# picoAvaR3.net
KiCad netlist of a schematic drawn in EAGLE
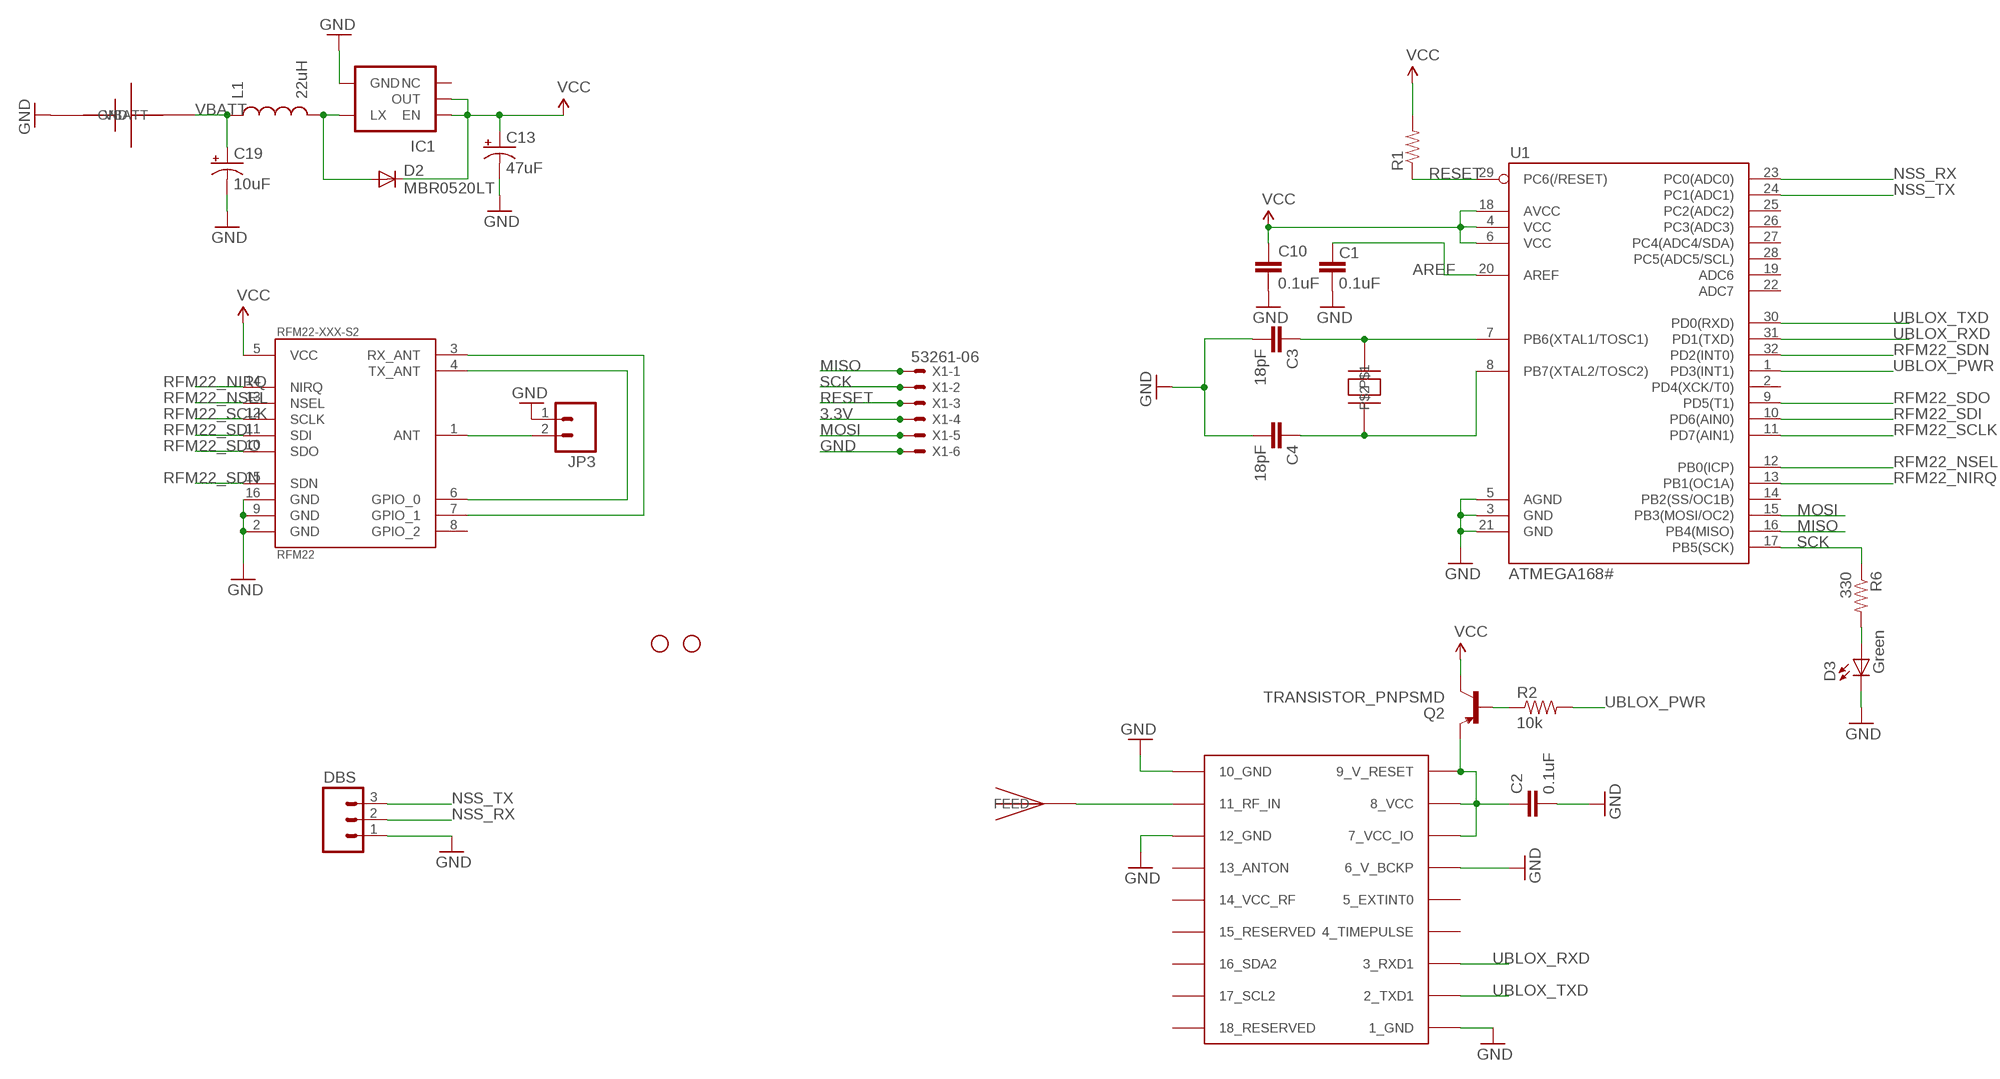
[diagram p0: schematic, sheet 1]

(export (version "E")
  (design (tool "Eeschema 10.0.6"))
  (components
    (comp (ref "C1")
      (value "0.1uF")
      (footprint "eagle-import:0402-CAP")
      (libsource (lib "eagle-import") (part "CAP0402-CAP"))
    )
    (comp (ref "C2")
      (value "0.1uF")
      (footprint "eagle-import:0402-CAP")
      (libsource (lib "eagle-import") (part "CAP0402-CAP"))
    )
    (comp (ref "C3")
      (value "18pF")
      (footprint "eagle-import:0402-CAP")
      (libsource (lib "eagle-import") (part "CAP0402-CAP"))
    )
    (comp (ref "C4")
      (value "18pF")
      (footprint "eagle-import:0402-CAP")
      (libsource (lib "eagle-import") (part "CAP0402-CAP"))
    )
    (comp (ref "C10")
      (value "0.1uF")
      (footprint "eagle-import:0402-CAP")
      (libsource (lib "eagle-import") (part "CAP0402-CAP"))
    )
    (comp (ref "C13")
      (value "47uF")
      (footprint "eagle-import:EIA3216")
      (libsource (lib "eagle-import") (part "CAP_POL1206"))
    )
    (comp (ref "C19")
      (value "10uF")
      (footprint "eagle-import:EIA3216")
      (libsource (lib "eagle-import") (part "CAP_POL1206"))
    )
    (comp (ref "D2")
      (value "MBR0520LT")
      (footprint "eagle-import:SOD123")
      (libsource (lib "eagle-import") (part "MBR0520LT"))
    )
    (comp (ref "D3")
      (value "Green")
      (footprint "eagle-import:LED-0603")
      (libsource (lib "eagle-import") (part "LED0603"))
    )
    (comp (ref "DBS")
      (value "M03PTH")
      (footprint "eagle-import:1X03")
      (libsource (lib "eagle-import") (part "M03PTH"))
    )
    (comp (ref "IC1")
      (value "V_REG_NCP1400SOT23-5")
      (footprint "eagle-import:SOT23-5")
      (libsource (lib "eagle-import") (part "V_REG_NCP1400SOT23-5"))
    )
    (comp (ref "JP1")
      (value "STAND-OFF")
      (footprint "eagle-import:STAND-OFF")
      (libsource (lib "eagle-import") (part "STAND-OFF"))
    )
    (comp (ref "JP2")
      (value "STAND-OFF")
      (footprint "eagle-import:STAND-OFF")
      (libsource (lib "eagle-import") (part "STAND-OFF"))
    )
    (comp (ref "JP3")
      (value "M02PTH")
      (footprint "eagle-import:1X02")
      (libsource (lib "eagle-import") (part "M02PTH"))
    )
    (comp (ref "L1")
      (value "22uH")
      (footprint "eagle-import:1210")
      (libsource (lib "eagle-import") (part "INDUCTOR1210"))
    )
    (comp (ref "Q2")
      (value "TRANSISTOR_PNPSMD")
      (footprint "eagle-import:SOT23-3")
      (libsource (lib "eagle-import") (part "TRANSISTOR_PNPSMD"))
    )
    (comp (ref "R1")
      (value "RESISTOR0402-RES")
      (footprint "eagle-import:0402-RES")
      (libsource (lib "eagle-import") (part "RESISTOR0402-RES"))
    )
    (comp (ref "R2")
      (value "10k")
      (footprint "eagle-import:0402-RES")
      (libsource (lib "eagle-import") (part "RESISTOR0402-RES"))
    )
    (comp (ref "R6")
      (value "330")
      (footprint "eagle-import:0402-RES")
      (libsource (lib "eagle-import") (part "RESISTOR0402-RES"))
    )
    (comp (ref "RFM22-XXX-S2")
      (value "RFM22")
      (footprint "eagle-import:RFM22-XXX-S2")
      (libsource (lib "eagle-import") (part "RFM22"))
    )
    (comp (ref "U$1")
      (value "UBLOX_MAX-6")
      (footprint "eagle-import:UBLOX_MAX-6")
      (libsource (lib "eagle-import") (part "UBLOX_MAX-6"))
    )
    (comp (ref "U$2")
      (value "ABRACON_ABM3_CRYSTAL")
      (footprint "eagle-import:ABRACON_ABM3_CRYSTAL")
      (libsource (lib "eagle-import") (part "ABRACON_ABM3_CRYSTAL"))
    )
    (comp (ref "U$3")
      (value "JTI_ANTENNA-1575AT43A40")
      (footprint "eagle-import:JTI_ANTENNA-1575AT43A40")
      (libsource (lib "eagle-import") (part "JTI_ANTENNA-1575AT43A40"))
    )
    (comp (ref "U$4")
      (value "KEYSTONE-82-AAA-BATTERY-HOLDER")
      (footprint "eagle-import:KEYSTONE-82-AAA-BATTERY")
      (libsource (lib "eagle-import") (part "KEYSTONE-82-AAA-BATTERY-HOLDER"))
    )
    (comp (ref "U1")
      (value "ATMEGA168#")
      (footprint "eagle-import:TQFP32-08")
      (libsource (lib "eagle-import") (part "ATMEGA168"))
    )
    (comp (ref "X1")
      (value "53261-06")
      (footprint "eagle-import:53261-06")
      (libsource (lib "eagle-import") (part "53?-06261"))
    )
  )
  (nets
    (net (code "1") (name "3.3V") (class "Default")
      (node (ref "C10") (pin "1") (pinfunction "1_1") (pintype "passive"))
      (node (ref "C13") (pin "A") (pinfunction "+_A") (pintype "passive"))
      (node (ref "D2") (pin "C") (pinfunction "C_C") (pintype "passive"))
      (node (ref "IC1") (pin "1") (pinfunction "EN_1") (pintype "input"))
      (node (ref "IC1") (pin "2") (pinfunction "OUT_2") (pintype "passive"))
      (node (ref "Q2") (pin "3") (pinfunction "C_3") (pintype "passive"))
      (node (ref "R1") (pin "2") (pinfunction "2_2") (pintype "passive"))
      (node (ref "RFM22-XXX-S2") (pin "5") (pinfunction "VCC_5") (pintype "bidirectional"))
      (node (ref "U1") (pin "18") (pinfunction "AVCC_18") (pintype "bidirectional"))
      (node (ref "U1") (pin "4") (pinfunction "VCC_4") (pintype "bidirectional"))
      (node (ref "U1") (pin "6") (pinfunction "VCC_6") (pintype "bidirectional"))
      (node (ref "X1") (pin "4") (pinfunction "S_4") (pintype "passive"))
    )
    (net (code "2") (name "AREF") (class "Default")
      (node (ref "C1") (pin "2") (pinfunction "2_2") (pintype "passive"))
      (node (ref "U1") (pin "20") (pinfunction "AREF_20") (pintype "bidirectional"))
    )
    (net (code "3") (name "GND") (class "Default")
      (node (ref "C1") (pin "1") (pinfunction "1_1") (pintype "passive"))
      (node (ref "C10") (pin "2") (pinfunction "2_2") (pintype "passive"))
      (node (ref "C13") (pin "C") (pinfunction "-_C") (pintype "passive"))
      (node (ref "C19") (pin "C") (pinfunction "-_C") (pintype "passive"))
      (node (ref "C2") (pin "2") (pinfunction "2_2") (pintype "passive"))
      (node (ref "C3") (pin "2") (pinfunction "2_2") (pintype "passive"))
      (node (ref "C4") (pin "2") (pinfunction "2_2") (pintype "passive"))
      (node (ref "D3") (pin "C") (pinfunction "C_C") (pintype "passive"))
      (node (ref "DBS") (pin "1") (pinfunction "1_1") (pintype "passive"))
      (node (ref "IC1") (pin "4") (pinfunction "GND_4") (pintype "input"))
      (node (ref "JP3") (pin "1") (pinfunction "1_1") (pintype "passive"))
      (node (ref "RFM22-XXX-S2") (pin "16") (pinfunction "GND_16") (pintype "power_in"))
      (node (ref "RFM22-XXX-S2") (pin "2") (pinfunction "GND_2") (pintype "power_in"))
      (node (ref "RFM22-XXX-S2") (pin "9") (pinfunction "GND_9") (pintype "power_in"))
      (node (ref "U$1") (pin "10_GND") (pinfunction "10_GND_10_GND") (pintype "bidirectional"))
      (node (ref "U$1") (pin "12_GND") (pinfunction "12_GND_12_GND") (pintype "bidirectional"))
      (node (ref "U$1") (pin "1_GND") (pinfunction "1_GND_1_GND") (pintype "bidirectional"))
      (node (ref "U$1") (pin "6_V_BCKP") (pinfunction "6_V_BCKP_6_V_BCKP") (pintype "bidirectional"))
      (node (ref "U$4") (pin "GND") (pinfunction "GND_GND") (pintype "bidirectional"))
      (node (ref "U$4") (pin "GND2") (pinfunction "GND_GND2") (pintype "bidirectional"))
      (node (ref "U1") (pin "21") (pinfunction "GND_21") (pintype "bidirectional"))
      (node (ref "U1") (pin "3") (pinfunction "GND_3") (pintype "bidirectional"))
      (node (ref "U1") (pin "5") (pinfunction "AGND_5") (pintype "bidirectional"))
      (node (ref "X1") (pin "6") (pinfunction "S_6") (pintype "passive"))
    )
    (net (code "4") (name "MISO") (class "Default")
      (node (ref "U1") (pin "16") (pinfunction "PB4(MISO)_16") (pintype "bidirectional"))
      (node (ref "X1") (pin "1") (pinfunction "S_1") (pintype "passive"))
    )
    (net (code "5") (name "MOSI") (class "Default")
      (node (ref "U1") (pin "15") (pinfunction "PB3(MOSI/OC2)_15") (pintype "bidirectional"))
      (node (ref "X1") (pin "5") (pinfunction "S_5") (pintype "passive"))
    )
    (net (code "6") (name "NSS_RX") (class "Default")
      (node (ref "DBS") (pin "2") (pinfunction "2_2") (pintype "passive"))
      (node (ref "U1") (pin "23") (pinfunction "PC0(ADC0)_23") (pintype "bidirectional"))
    )
    (net (code "7") (name "NSS_TX") (class "Default")
      (node (ref "DBS") (pin "3") (pinfunction "3_3") (pintype "passive"))
      (node (ref "U1") (pin "24") (pinfunction "PC1(ADC1)_24") (pintype "bidirectional"))
    )
    (net (code "8") (name "Net-(D3-PadA)") (class "Default")
      (node (ref "D3") (pin "A") (pinfunction "A_A") (pintype "passive"))
      (node (ref "R6") (pin "2") (pinfunction "2_2") (pintype "passive"))
    )
    (net (code "9") (name "Net-(IC1-LX)") (class "Default")
      (node (ref "D2") (pin "A") (pinfunction "A_A") (pintype "passive"))
      (node (ref "IC1") (pin "5") (pinfunction "LX_5") (pintype "input"))
      (node (ref "L1") (pin "2") (pinfunction "2_2") (pintype "passive"))
    )
    (net (code "10") (name "Net-(Q2-B)") (class "Default")
      (node (ref "Q2") (pin "1") (pinfunction "B_1") (pintype "passive"))
      (node (ref "R2") (pin "1") (pinfunction "1_1") (pintype "passive"))
    )
    (net (code "11") (name "Net-(Q2-E)") (class "Default")
      (node (ref "C2") (pin "1") (pinfunction "1_1") (pintype "passive"))
      (node (ref "Q2") (pin "2") (pinfunction "E_2") (pintype "passive"))
      (node (ref "U$1") (pin "7_VCC_IO") (pinfunction "7_VCC_IO_7_VCC_IO") (pintype "bidirectional"))
      (node (ref "U$1") (pin "8_VCC") (pinfunction "8_VCC_8_VCC") (pintype "bidirectional"))
      (node (ref "U$1") (pin "9_V_RESET") (pinfunction "9_V_RESET_9_V_RESET") (pintype "bidirectional"))
    )
    (net (code "12") (name "Net-(RFM22-XXX-S2-ANT)") (class "Default")
      (node (ref "JP3") (pin "2") (pinfunction "2_2") (pintype "passive"))
      (node (ref "RFM22-XXX-S2") (pin "1") (pinfunction "ANT_1") (pintype "bidirectional"))
    )
    (net (code "13") (name "Net-(RFM22-XXX-S2-GPIO_0)") (class "Default")
      (node (ref "RFM22-XXX-S2") (pin "4") (pinfunction "TX_ANT_4") (pintype "input"))
      (node (ref "RFM22-XXX-S2") (pin "6") (pinfunction "GPIO_0_6") (pintype "bidirectional"))
    )
    (net (code "14") (name "Net-(RFM22-XXX-S2-GPIO_1)") (class "Default")
      (node (ref "RFM22-XXX-S2") (pin "3") (pinfunction "RX_ANT_3") (pintype "input"))
      (node (ref "RFM22-XXX-S2") (pin "7") (pinfunction "GPIO_1_7") (pintype "bidirectional"))
    )
    (net (code "15") (name "Net-(U$1-Pad11_RF_IN)") (class "Default")
      (node (ref "U$1") (pin "11_RF_IN") (pinfunction "11_RF_IN_11_RF_IN") (pintype "bidirectional"))
      (node (ref "U$3") (pin "FEED") (pinfunction "FEED_FEED") (pintype "bidirectional"))
    )
    (net (code "16") (name "Net-(U1-PB6(XTAL1{slash}TOSC1))") (class "Default")
      (node (ref "C3") (pin "1") (pinfunction "1_1") (pintype "passive"))
      (node (ref "U$2") (pin "P$2") (pinfunction "P$2_P$2") (pintype "bidirectional"))
      (node (ref "U1") (pin "7") (pinfunction "PB6(XTAL1/TOSC1)_7") (pintype "bidirectional"))
    )
    (net (code "17") (name "Net-(U1-PB7(XTAL2{slash}TOSC2))") (class "Default")
      (node (ref "C4") (pin "1") (pinfunction "1_1") (pintype "passive"))
      (node (ref "U$2") (pin "P$1") (pinfunction "P$1_P$1") (pintype "bidirectional"))
      (node (ref "U1") (pin "8") (pinfunction "PB7(XTAL2/TOSC2)_8") (pintype "bidirectional"))
    )
    (net (code "18") (name "RESET") (class "Default")
      (node (ref "R1") (pin "1") (pinfunction "1_1") (pintype "passive"))
      (node (ref "U1") (pin "29") (pinfunction "PC6(/RESET)_29") (pintype "bidirectional"))
      (node (ref "X1") (pin "3") (pinfunction "S_3") (pintype "passive"))
    )
    (net (code "19") (name "RFM22_NIRQ") (class "Default")
      (node (ref "RFM22-XXX-S2") (pin "14") (pinfunction "NIRQ_14") (pintype "output"))
      (node (ref "U1") (pin "13") (pinfunction "PB1(OC1A)_13") (pintype "bidirectional"))
    )
    (net (code "20") (name "RFM22_NSEL") (class "Default")
      (node (ref "RFM22-XXX-S2") (pin "13") (pinfunction "NSEL_13") (pintype "input"))
      (node (ref "U1") (pin "12") (pinfunction "PB0(ICP)_12") (pintype "bidirectional"))
    )
    (net (code "21") (name "RFM22_SCLK") (class "Default")
      (node (ref "RFM22-XXX-S2") (pin "12") (pinfunction "SCLK_12") (pintype "input"))
      (node (ref "U1") (pin "11") (pinfunction "PD7(AIN1)_11") (pintype "bidirectional"))
    )
    (net (code "22") (name "RFM22_SDI") (class "Default")
      (node (ref "RFM22-XXX-S2") (pin "11") (pinfunction "SDI_11") (pintype "input"))
      (node (ref "U1") (pin "10") (pinfunction "PD6(AIN0)_10") (pintype "bidirectional"))
    )
    (net (code "23") (name "RFM22_SDN") (class "Default")
      (node (ref "RFM22-XXX-S2") (pin "15") (pinfunction "SDN_15") (pintype "input"))
      (node (ref "U1") (pin "32") (pinfunction "PD2(INT0)_32") (pintype "bidirectional"))
    )
    (net (code "24") (name "RFM22_SDO") (class "Default")
      (node (ref "RFM22-XXX-S2") (pin "10") (pinfunction "SDO_10") (pintype "output"))
      (node (ref "U1") (pin "9") (pinfunction "PD5(T1)_9") (pintype "bidirectional"))
    )
    (net (code "25") (name "SCK") (class "Default")
      (node (ref "R6") (pin "1") (pinfunction "1_1") (pintype "passive"))
      (node (ref "U1") (pin "17") (pinfunction "PB5(SCK)_17") (pintype "bidirectional"))
      (node (ref "X1") (pin "2") (pinfunction "S_2") (pintype "passive"))
    )
    (net (code "26") (name "UBLOX_PWR") (class "Default")
      (node (ref "R2") (pin "2") (pinfunction "2_2") (pintype "passive"))
      (node (ref "U1") (pin "1") (pinfunction "PD3(INT1)_1") (pintype "bidirectional"))
    )
    (net (code "27") (name "UBLOX_RXD") (class "Default")
      (node (ref "U$1") (pin "3_RXD1") (pinfunction "3_RXD1_3_RXD1") (pintype "bidirectional"))
      (node (ref "U1") (pin "31") (pinfunction "PD1(TXD)_31") (pintype "bidirectional"))
    )
    (net (code "28") (name "UBLOX_TXD") (class "Default")
      (node (ref "U$1") (pin "2_TXD1") (pinfunction "2_TXD1_2_TXD1") (pintype "bidirectional"))
      (node (ref "U1") (pin "30") (pinfunction "PD0(RXD)_30") (pintype "bidirectional"))
    )
    (net (code "29") (name "VBATT") (class "Default")
      (node (ref "C19") (pin "A") (pinfunction "+_A") (pintype "passive"))
      (node (ref "L1") (pin "1") (pinfunction "1_1") (pintype "passive"))
      (node (ref "U$4") (pin "VBATT") (pinfunction "VBATT_VBATT") (pintype "bidirectional"))
      (node (ref "U$4") (pin "VBATT1") (pinfunction "VBATT_VBATT1") (pintype "bidirectional"))
    )
    (net (code "30") (name "unconnected-(IC1-NC-Pad3)") (class "Default")
      (node (ref "IC1") (pin "3") (pinfunction "NC_3") (pintype "input"))
    )
    (net (code "31") (name "unconnected-(RFM22-XXX-S2-GPIO_2-Pad8)") (class "Default")
      (node (ref "RFM22-XXX-S2") (pin "8") (pinfunction "GPIO_2_8") (pintype "bidirectional"))
    )
    (net (code "32") (name "unconnected-(U$1-Pad4_TIMEPULSE)") (class "Default")
      (node (ref "U$1") (pin "4_TIMEPULSE") (pinfunction "4_TIMEPULSE_4_TIMEPULSE") (pintype "bidirectional"))
    )
    (net (code "33") (name "unconnected-(U$1-Pad5_EXTINT0)") (class "Default")
      (node (ref "U$1") (pin "5_EXTINT0") (pinfunction "5_EXTINT0_5_EXTINT0") (pintype "bidirectional"))
    )
    (net (code "34") (name "unconnected-(U$1-Pad13_ANTON)") (class "Default")
      (node (ref "U$1") (pin "13_ANTON") (pinfunction "13_ANTON_13_ANTON") (pintype "bidirectional"))
    )
    (net (code "35") (name "unconnected-(U$1-Pad14_VCC_RF)") (class "Default")
      (node (ref "U$1") (pin "14_VCC_RF") (pinfunction "14_VCC_RF_14_VCC_RF") (pintype "bidirectional"))
    )
    (net (code "36") (name "unconnected-(U$1-Pad15_RESERVED)") (class "Default")
      (node (ref "U$1") (pin "15_RESERVED") (pinfunction "15_RESERVED_15_RESERVED") (pintype "bidirectional"))
    )
    (net (code "37") (name "unconnected-(U$1-Pad16_SDA2)") (class "Default")
      (node (ref "U$1") (pin "16_SDA2") (pinfunction "16_SDA2_16_SDA2") (pintype "bidirectional"))
    )
    (net (code "38") (name "unconnected-(U$1-Pad17_SCL2)") (class "Default")
      (node (ref "U$1") (pin "17_SCL2") (pinfunction "17_SCL2_17_SCL2") (pintype "bidirectional"))
    )
    (net (code "39") (name "unconnected-(U$1-Pad18_RESERVED)") (class "Default")
      (node (ref "U$1") (pin "18_RESERVED") (pinfunction "18_RESERVED_18_RESERVED") (pintype "bidirectional"))
    )
    (net (code "40") (name "unconnected-(U1-ADC6-Pad19)") (class "Default")
      (node (ref "U1") (pin "19") (pinfunction "ADC6_19") (pintype "bidirectional"))
    )
    (net (code "41") (name "unconnected-(U1-ADC7-Pad22)") (class "Default")
      (node (ref "U1") (pin "22") (pinfunction "ADC7_22") (pintype "bidirectional"))
    )
    (net (code "42") (name "unconnected-(U1-PB2(SS{slash}OC1B)-Pad14)") (class "Default")
      (node (ref "U1") (pin "14") (pinfunction "PB2(SS/OC1B)_14") (pintype "bidirectional"))
    )
    (net (code "43") (name "unconnected-(U1-PC2(ADC2)-Pad25)") (class "Default")
      (node (ref "U1") (pin "25") (pinfunction "PC2(ADC2)_25") (pintype "bidirectional"))
    )
    (net (code "44") (name "unconnected-(U1-PC3(ADC3)-Pad26)") (class "Default")
      (node (ref "U1") (pin "26") (pinfunction "PC3(ADC3)_26") (pintype "bidirectional"))
    )
    (net (code "45") (name "unconnected-(U1-PC4(ADC4{slash}SDA)-Pad27)") (class "Default")
      (node (ref "U1") (pin "27") (pinfunction "PC4(ADC4/SDA)_27") (pintype "bidirectional"))
    )
    (net (code "46") (name "unconnected-(U1-PC5(ADC5{slash}SCL)-Pad28)") (class "Default")
      (node (ref "U1") (pin "28") (pinfunction "PC5(ADC5/SCL)_28") (pintype "bidirectional"))
    )
    (net (code "47") (name "unconnected-(U1-PD4(XCK{slash}T0)-Pad2)") (class "Default")
      (node (ref "U1") (pin "2") (pinfunction "PD4(XCK/T0)_2") (pintype "bidirectional"))
    )
  )
)
